# shield.net
KiCad netlist of a schematic drawn in Altium Designer
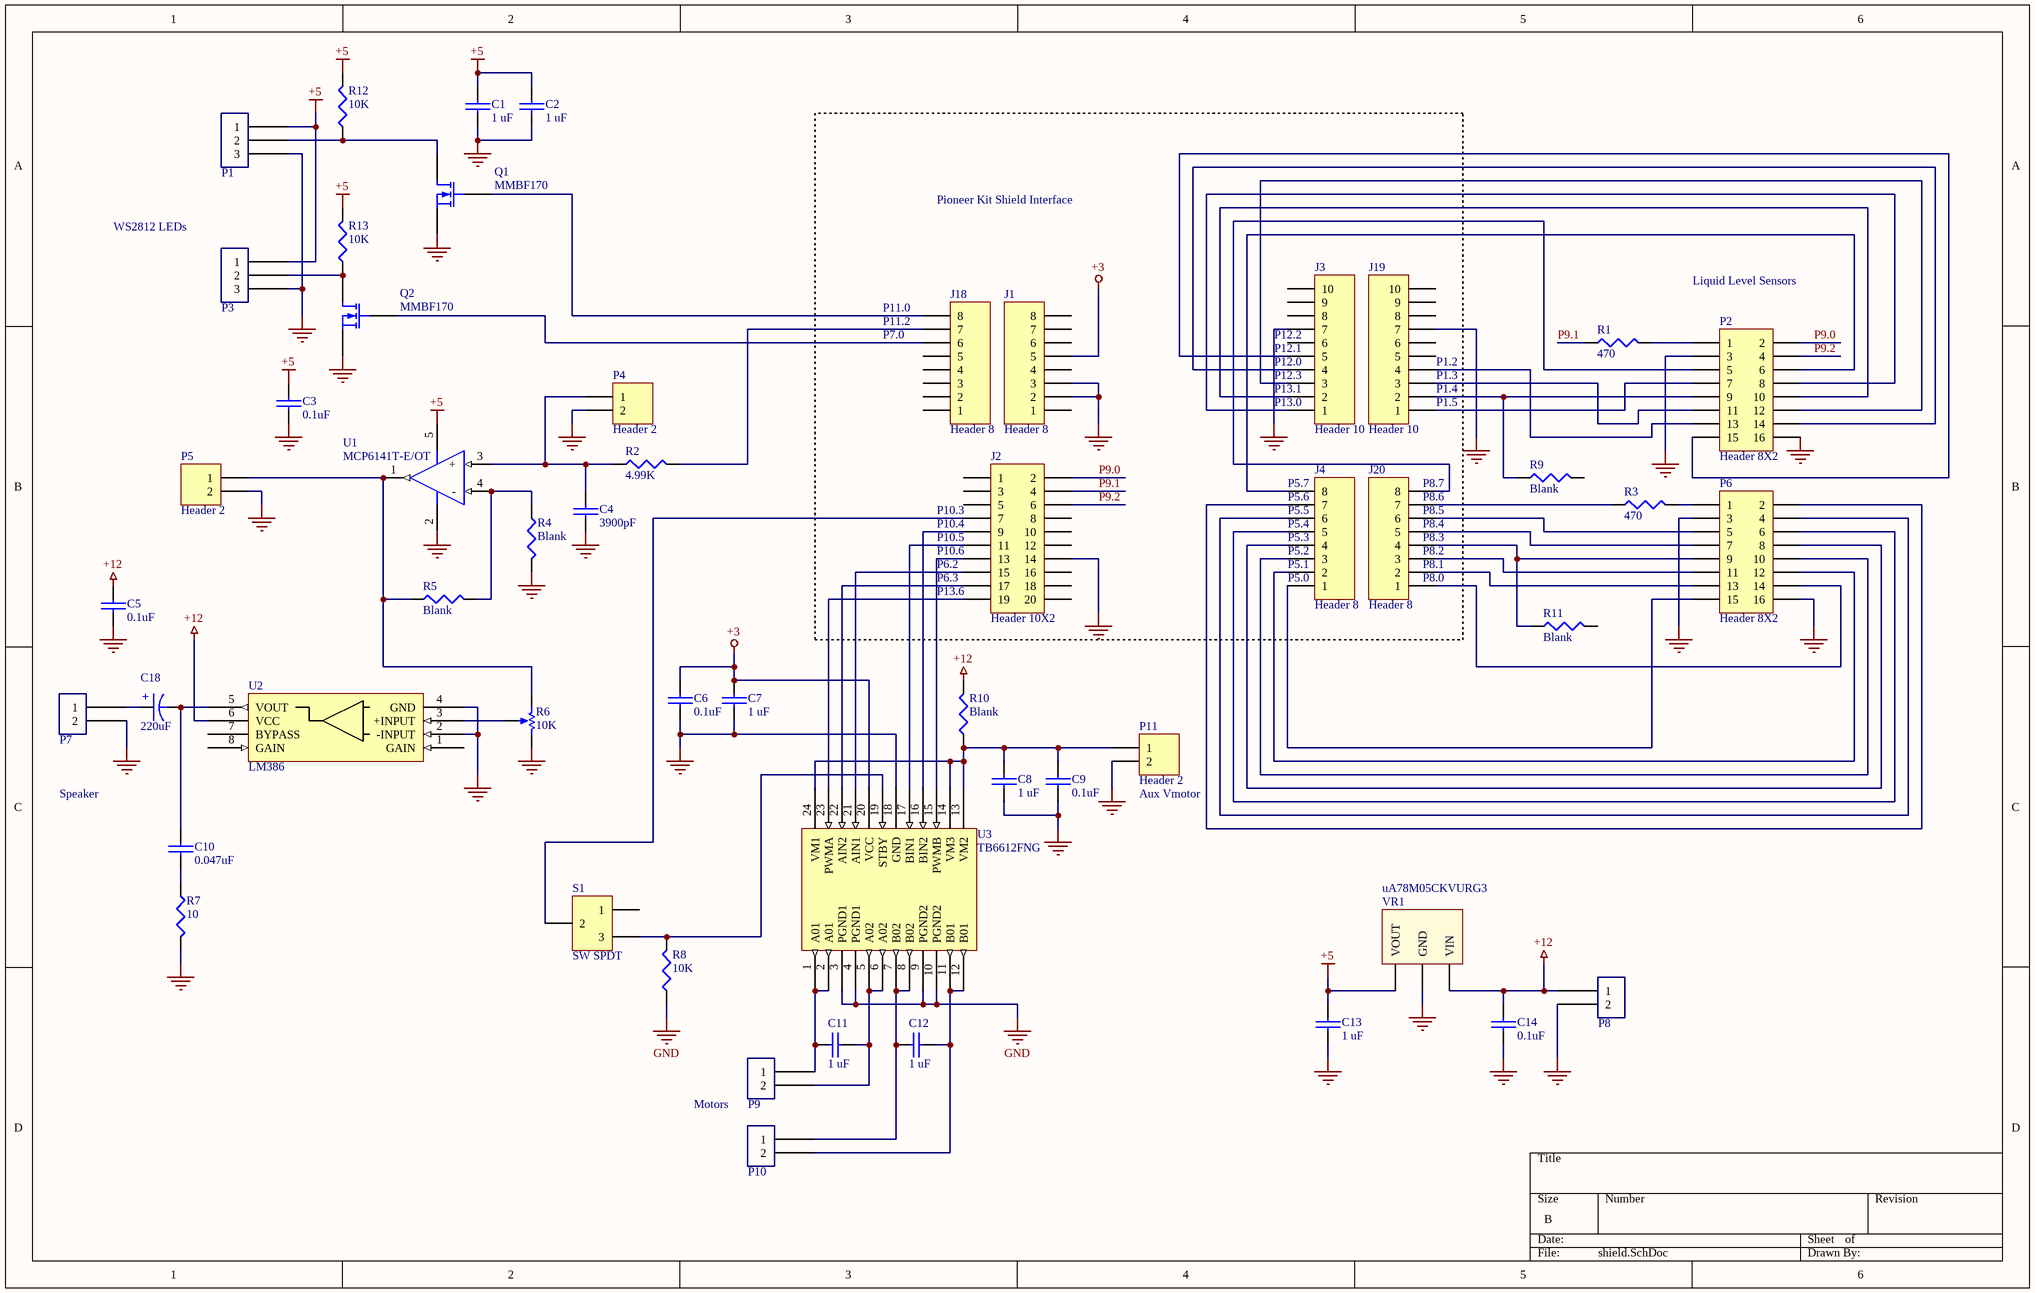
[diagram p0: shield.SchDoc]

(export (version "E")
  (design (tool "Eeschema 10.0.6"))
  (components
    (comp (ref "C1")
      (value "1 uF")
      (footprint "C0805")
      (description "CAP, CER, 1UF, 16v, 10%, X5R, 0805")
      (libsource (lib "phantron-discretes") (part "CAP, CER, 1UF, 0805"))
    )
    (comp (ref "C2")
      (value "1 uF")
      (footprint "C0805")
      (description "CAP, CER, 1UF, 16v, 10%, X5R, 0805")
      (libsource (lib "phantron-discretes") (part "CAP, CER, 1UF, 0805"))
    )
    (comp (ref "C3")
      (value "0.1uF")
      (footprint "C0603")
      (description "CAP, CER, 0.1UF, 50V, 10%, X7R, 0603")
      (libsource (lib "phantron-discretes") (part "CAP, CER, 0.1uF 0603"))
    )
    (comp (ref "C4")
      (value "3900pF")
      (footprint "C0603")
      (description "CAP, CER, blankUF, 6.3v, 10%, X5R, 0603")
      (libsource (lib "phantron-discretes") (part "CAP, CER, BLANK, 0603"))
    )
    (comp (ref "C5")
      (value "0.1uF")
      (footprint "C0603")
      (description "CAP, CER, 0.1UF, 50V, 10%, X7R, 0603")
      (libsource (lib "phantron-discretes") (part "CAP, CER, 0.1uF 0603"))
    )
    (comp (ref "C6")
      (value "0.1uF")
      (footprint "C0603")
      (description "CAP, CER, 0.1UF, 50V, 10%, X7R, 0603")
      (libsource (lib "phantron-discretes") (part "CAP, CER, 0.1uF 0603"))
    )
    (comp (ref "C7")
      (value "1 uF")
      (footprint "C0805")
      (description "CAP, CER, 1UF, 16v, 10%, X5R, 0805")
      (libsource (lib "phantron-discretes") (part "CAP, CER, 1UF, 0805"))
    )
    (comp (ref "C8")
      (value "1 uF")
      (footprint "C0805")
      (description "CAP, CER, 1UF, 16v, 10%, X5R, 0805")
      (libsource (lib "phantron-discretes") (part "CAP, CER, 1UF, 0805"))
    )
    (comp (ref "C9")
      (value "0.1uF")
      (footprint "C0603")
      (description "CAP, CER, 0.1UF, 50V, 10%, X7R, 0603")
      (libsource (lib "phantron-discretes") (part "CAP, CER, 0.1uF 0603"))
    )
    (comp (ref "C10")
      (value "0.047uF")
      (footprint "C0603")
      (description "CAP, CER, blankUF, 6.3v, 10%, X5R, 0603")
      (libsource (lib "phantron-discretes") (part "CAP, CER, BLANK, 0603"))
    )
    (comp (ref "C11")
      (value "1 uF")
      (footprint "C0805")
      (description "CAP, CER, 1UF, 16v, 10%, X5R, 0805")
      (libsource (lib "phantron-discretes") (part "CAP, CER, 1UF, 0805"))
    )
    (comp (ref "C12")
      (value "1 uF")
      (footprint "C0805")
      (description "CAP, CER, 1UF, 16v, 10%, X5R, 0805")
      (libsource (lib "phantron-discretes") (part "CAP, CER, 1UF, 0805"))
    )
    (comp (ref "C13")
      (value "1 uF")
      (footprint "C0805")
      (description "CAP, CER, 1UF, 16v, 10%, X5R, 0805")
      (libsource (lib "phantron-discretes") (part "CAP, CER, 1UF, 0805"))
    )
    (comp (ref "C14")
      (value "0.1uF")
      (footprint "C0603")
      (description "CAP, CER, 0.1UF, 50V, 10%, X7R, 0603")
      (libsource (lib "phantron-discretes") (part "CAP, CER, 0.1uF 0603"))
    )
    (comp (ref "C18")
      (value "220uF")
      (footprint "RadCap.98")
      (description "CAP, 220uF, 10V, ELEC, RAD")
      (fields (field (name "Comment") "11-000010-ARD"))
      (libsource (lib "00000000") (part "11-000010-ARD"))
    )
    (comp (ref "J1")
      (value "Header 8")
      (footprint "HDR1X8")
      (description "Header, 8-Pin")
      (fields (field (name "PUBLISHER") "Altium Limited"))
      (libsource (lib "Miscellaneous Connectors") (part "Header 8"))
    )
    (comp (ref "J2")
      (value "Header 10X2")
      (footprint "HDR2X10")
      (description "Header, 10-Pin, Dual row")
      (fields (field (name "PUBLISHER") "Altium Limited"))
      (libsource (lib "Miscellaneous Connectors") (part "Header 10X2"))
    )
    (comp (ref "J3")
      (value "Header 10")
      (footprint "HDR1X10")
      (description "Header, 10-Pin")
      (fields (field (name "PUBLISHER") "Altium Limited"))
      (libsource (lib "") (part "Header 10_1"))
    )
    (comp (ref "J4")
      (value "Header 8")
      (footprint "HDR1X8")
      (description "Header, 8-Pin")
      (fields (field (name "PUBLISHER") "Altium Limited"))
      (libsource (lib "") (part "Header 8_1"))
    )
    (comp (ref "J18")
      (value "Header 8")
      (footprint "HDR1X8")
      (description "Header, 8-Pin")
      (fields (field (name "PUBLISHER") "Altium Limited"))
      (libsource (lib "") (part "Header 8_1"))
    )
    (comp (ref "J19")
      (value "Header 10")
      (footprint "HDR1X10")
      (description "Header, 10-Pin")
      (fields (field (name "PUBLISHER") "Altium Limited"))
      (libsource (lib "Miscellaneous Connectors") (part "Header 10"))
    )
    (comp (ref "J20")
      (value "Header 8")
      (footprint "HDR1X8")
      (description "Header, 8-Pin")
      (fields (field (name "PUBLISHER") "Altium Limited"))
      (libsource (lib "Miscellaneous Connectors") (part "Header 8"))
    )
    (comp (ref "P1")
      (value "Connector, 0.138\", 3")
      (footprint "Phantron:connector-0.138-3pin")
      (description "Connector, 0.138\", 3 pin")
      (libsource (lib "Phantron") (part "Connector, 0.138{dblquote}, 3"))
    )
    (comp (ref "P2")
      (value "Header 8X2")
      (footprint "HDR2X8")
      (description "Header, 8-Pin, Dual row")
      (fields (field (name "PUBLISHER") "Altium Limited"))
      (libsource (lib "Miscellaneous Connectors") (part "Header 8X2"))
    )
    (comp (ref "P3")
      (value "Connector, 0.138\", 3")
      (footprint "Phantron:connector-0.138-3pin")
      (description "Connector, 0.138\", 3 pin")
      (libsource (lib "Phantron") (part "Connector, 0.138{dblquote}, 3"))
    )
    (comp (ref "P4")
      (value "Header 2")
      (footprint "HDR1X2")
      (description "Header, 2-Pin")
      (fields (field (name "PUBLISHER") "Altium Limited"))
      (libsource (lib "Miscellaneous Connectors") (part "Header 2"))
    )
    (comp (ref "P5")
      (value "Header 2")
      (footprint "HDR1X2")
      (description "Header, 2-Pin")
      (fields (field (name "PUBLISHER") "Altium Limited"))
      (libsource (lib "") (part "Header 2_1"))
    )
    (comp (ref "P6")
      (value "Header 8X2")
      (footprint "HDR2X8")
      (description "Header, 8-Pin, Dual row")
      (fields (field (name "PUBLISHER") "Altium Limited"))
      (libsource (lib "Miscellaneous Connectors") (part "Header 8X2"))
    )
    (comp (ref "P7")
      (value "Connector, 0.138\", 2")
      (footprint "Phantron:connector-0.138-2pin")
      (description "Connector, 0.138\", 2 pin")
      (libsource (lib "") (part "Connector, 0.138{dblquote}, 2_1"))
    )
    (comp (ref "P8")
      (value "Connector, 0.138\", 2")
      (footprint "Phantron:connector-0.138-2pin")
      (description "Connector, 0.138\", 2 pin")
      (libsource (lib "Phantron") (part "Connector, 0.138{dblquote}, 2"))
    )
    (comp (ref "P9")
      (value "Connector, 0.138\", 2")
      (footprint "Phantron:connector-0.138-2pin")
      (description "Connector, 0.138\", 2 pin")
      (libsource (lib "") (part "Connector, 0.138{dblquote}, 2_1"))
    )
    (comp (ref "P10")
      (value "Connector, 0.138\", 2")
      (footprint "Phantron:connector-0.138-2pin")
      (description "Connector, 0.138\", 2 pin")
      (libsource (lib "") (part "Connector, 0.138{dblquote}, 2_1"))
    )
    (comp (ref "P11")
      (value "Header 2")
      (footprint "HDR1X2")
      (description "Header, 2-Pin")
      (fields (field (name "PUBLISHER") "Altium Limited"))
      (libsource (lib "Miscellaneous Connectors") (part "Header 2"))
    )
    (comp (ref "Q1")
      (value "MMBF170")
      (footprint "SOT23")
      (description "MMBF170-7-F")
      (libsource (lib "Phantron") (part "MMBF170-7-F"))
    )
    (comp (ref "Q2")
      (value "MMBF170")
      (footprint "SOT23")
      (description "MMBF170-7-F")
      (libsource (lib "Phantron") (part "MMBF170-7-F"))
    )
    (comp (ref "R1")
      (value "470")
      (footprint "R0603")
      (description "RES, BLANK OHM, 1/10W, 1%, 0603 SMD")
      (libsource (lib "phantron-discretes") (part "RES, BLANK, 0603"))
    )
    (comp (ref "R2")
      (value "4.99K")
      (footprint "R0603")
      (description "RES, BLANK OHM, 1/10W, 1%, 0603 SMD")
      (libsource (lib "phantron-discretes") (part "RES, BLANK, 0603"))
    )
    (comp (ref "R3")
      (value "470")
      (footprint "R0603")
      (description "RES, BLANK OHM, 1/10W, 1%, 0603 SMD")
      (libsource (lib "phantron-discretes") (part "RES, BLANK, 0603"))
    )
    (comp (ref "R4")
      (value "Blank")
      (footprint "R0603")
      (description "RES, BLANK OHM, 1/10W, 1%, 0603 SMD")
      (libsource (lib "phantron-discretes") (part "RES, BLANK, 0603"))
    )
    (comp (ref "R5")
      (value "Blank")
      (footprint "R0603")
      (description "RES, BLANK OHM, 1/10W, 1%, 0603 SMD")
      (libsource (lib "phantron-discretes") (part "RES, BLANK, 0603"))
    )
    (comp (ref "R6")
      (value "10K")
      (footprint "TrimmerPot")
      (description "Potentiometer")
      (fields (field (name "Comment") "RPot") (field (name "PUBLISHER") "Altium Limited"))
      (libsource (lib "Miscellaneous Devices") (part "RPot"))
    )
    (comp (ref "R7")
      (value "10")
      (footprint "R0603")
      (description "RES, BLANK OHM, 1/10W, 1%, 0603 SMD")
      (libsource (lib "phantron-discretes") (part "RES, BLANK, 0603"))
    )
    (comp (ref "R8")
      (value "10K")
      (footprint "R0603")
      (description "RES, BLANK OHM, 1/10W, 1%, 0603 SMD")
      (libsource (lib "phantron-discretes") (part "RES, BLANK, 0603"))
    )
    (comp (ref "R9")
      (value "Blank")
      (footprint "R0603")
      (description "RES, BLANK OHM, 1/10W, 1%, 0603 SMD")
      (libsource (lib "phantron-discretes") (part "RES, BLANK, 0603"))
    )
    (comp (ref "R10")
      (value "Blank")
      (footprint "R0603")
      (description "RES, BLANK OHM, 1/10W, 1%, 0603 SMD")
      (libsource (lib "phantron-discretes") (part "RES, BLANK, 0603"))
    )
    (comp (ref "R11")
      (value "Blank")
      (footprint "R0603")
      (description "RES, BLANK OHM, 1/10W, 1%, 0603 SMD")
      (libsource (lib "phantron-discretes") (part "RES, BLANK, 0603"))
    )
    (comp (ref "R12")
      (value "10K")
      (footprint "R0603")
      (description "RES, BLANK OHM, 1/10W, 1%, 0603 SMD")
      (libsource (lib "phantron-discretes") (part "RES, BLANK, 0603"))
    )
    (comp (ref "R13")
      (value "10K")
      (footprint "R0603")
      (description "RES, BLANK OHM, 1/10W, 1%, 0603 SMD")
      (libsource (lib "phantron-discretes") (part "RES, BLANK, 0603"))
    )
    (comp (ref "S1")
      (value "SW SPDT")
      (footprint "HDR1X3")
      (description "Header, 3-Pin")
      (fields (field (name "PUBLISHER") "Altium Limited"))
      (libsource (lib "Miscellaneous Connectors") (part "Header 3"))
    )
    (comp (ref "U1")
      (value "MCP6141T-E/OT")
      (footprint "SOT23-5")
      (description "IC OPAMP SINGLE MCP6141 SOT23-5")
      (fields (field (name "MFG") "Microchip"))
      (libsource (lib "Phantron") (part "MCP6141"))
    )
    (comp (ref "U2")
      (value "LM386")
      (footprint "Phantron:SO8")
      (description "LM386MX")
      (fields (field (name "MFG") "TI"))
      (libsource (lib "Phantron") (part "LM386MX"))
    )
    (comp (ref "U3")
      (value "TB6612FNG")
      (footprint "Phantron:SSOP-24")
      (fields (field (name "MFG") "Toshiba"))
      (libsource (lib "Phantron") (part "TB6612FNG"))
    )
    (comp (ref "VR1")
      (value "uA78M05CKVURG3")
      (footprint "TO-252-AB(Dpak)")
      (libsource (lib "Phantron") (part "uA78M05CKVURG3"))
    )
  )
  (nets
    (net (code "1") (name "+3") (class "Default")
      (node (ref "C6") (pin "1") (pinfunction "A_1") (pintype "passive"))
      (node (ref "C7") (pin "1") (pinfunction "A_1") (pintype "passive"))
      (node (ref "J1") (pin "5") (pinfunction "5_5") (pintype "passive"))
      (node (ref "U3") (pin "20") (pinfunction "VCC_20") (pintype "power_in"))
    )
    (net (code "2") (name "+5") (class "Default")
      (node (ref "C1") (pin "1") (pinfunction "A_1") (pintype "passive"))
      (node (ref "C13") (pin "1") (pinfunction "A_1") (pintype "passive"))
      (node (ref "C2") (pin "1") (pinfunction "A_1") (pintype "passive"))
      (node (ref "C3") (pin "1") (pinfunction "A_1") (pintype "passive"))
      (node (ref "P1") (pin "1") (pinfunction "1_1") (pintype "passive"))
      (node (ref "P3") (pin "1") (pinfunction "1_1") (pintype "passive"))
      (node (ref "R12") (pin "2") (pinfunction "B_2") (pintype "passive"))
      (node (ref "R13") (pin "2") (pinfunction "B_2") (pintype "passive"))
      (node (ref "U1") (pin "5") (pinfunction "VCC_5") (pintype "power_in"))
      (node (ref "VR1") (pin "3") (pinfunction "VOUT_3") (pintype "passive"))
    )
    (net (code "3") (name "+12") (class "Default")
      (node (ref "C14") (pin "1") (pinfunction "A_1") (pintype "passive"))
      (node (ref "C5") (pin "1") (pinfunction "A_1") (pintype "passive"))
      (node (ref "P8") (pin "1") (pinfunction "1_1") (pintype "passive"))
      (node (ref "R10") (pin "2") (pinfunction "B_2") (pintype "passive"))
      (node (ref "U2") (pin "6") (pinfunction "VCC_6") (pintype "power_in"))
      (node (ref "VR1") (pin "1") (pinfunction "VIN_1") (pintype "passive"))
    )
    (net (code "4") (name "/P9.0") (class "Default")
      (node (ref "J2") (pin "2") (pinfunction "2_2") (pintype "passive"))
      (node (ref "P2") (pin "2") (pinfunction "2_2") (pintype "passive"))
    )
    (net (code "5") (name "/P9.1") (class "Default")
      (node (ref "J2") (pin "4") (pinfunction "4_4") (pintype "passive"))
      (node (ref "R1") (pin "1") (pinfunction "A_1") (pintype "passive"))
    )
    (net (code "6") (name "/P9.2") (class "Default")
      (node (ref "J2") (pin "6") (pinfunction "6_6") (pintype "passive"))
      (node (ref "P2") (pin "4") (pinfunction "4_4") (pintype "passive"))
    )
    (net (code "7") (name "GND") (class "Default")
      (node (ref "C1") (pin "2") (pinfunction "B_2") (pintype "passive"))
      (node (ref "C13") (pin "2") (pinfunction "B_2") (pintype "passive"))
      (node (ref "C14") (pin "2") (pinfunction "B_2") (pintype "passive"))
      (node (ref "C2") (pin "2") (pinfunction "B_2") (pintype "passive"))
      (node (ref "C3") (pin "2") (pinfunction "B_2") (pintype "passive"))
      (node (ref "C4") (pin "2") (pinfunction "B_2") (pintype "passive"))
      (node (ref "C5") (pin "2") (pinfunction "B_2") (pintype "passive"))
      (node (ref "C6") (pin "2") (pinfunction "B_2") (pintype "passive"))
      (node (ref "C7") (pin "2") (pinfunction "B_2") (pintype "passive"))
      (node (ref "C8") (pin "2") (pinfunction "B_2") (pintype "passive"))
      (node (ref "C9") (pin "2") (pinfunction "B_2") (pintype "passive"))
      (node (ref "J1") (pin "2") (pinfunction "2_2") (pintype "passive"))
      (node (ref "J1") (pin "3") (pinfunction "3_3") (pintype "passive"))
      (node (ref "J19") (pin "7") (pinfunction "7_7") (pintype "passive"))
      (node (ref "J2") (pin "14") (pinfunction "14_14") (pintype "passive"))
      (node (ref "J3") (pin "7") (pinfunction "7_7") (pintype "passive"))
      (node (ref "P1") (pin "3") (pinfunction "3_3") (pintype "passive"))
      (node (ref "P11") (pin "2") (pinfunction "2_2") (pintype "passive"))
      (node (ref "P2") (pin "16") (pinfunction "16_16") (pintype "passive"))
      (node (ref "P2") (pin "3") (pinfunction "3_3") (pintype "passive"))
      (node (ref "P3") (pin "3") (pinfunction "3_3") (pintype "passive"))
      (node (ref "P4") (pin "2") (pinfunction "2_2") (pintype "passive"))
      (node (ref "P5") (pin "2") (pinfunction "2_2") (pintype "passive"))
      (node (ref "P6") (pin "16") (pinfunction "16_16") (pintype "passive"))
      (node (ref "P6") (pin "3") (pinfunction "3_3") (pintype "passive"))
      (node (ref "P7") (pin "2") (pinfunction "2_2") (pintype "passive"))
      (node (ref "P8") (pin "2") (pinfunction "2_2") (pintype "passive"))
      (node (ref "Q1") (pin "2") (pinfunction "S_2") (pintype "passive"))
      (node (ref "Q2") (pin "2") (pinfunction "S_2") (pintype "passive"))
      (node (ref "R4") (pin "2") (pinfunction "B_2") (pintype "passive"))
      (node (ref "R6") (pin "1") (pinfunction "TOP_1") (pintype "passive"))
      (node (ref "R7") (pin "2") (pinfunction "B_2") (pintype "passive"))
      (node (ref "R8") (pin "1") (pinfunction "A_1") (pintype "passive"))
      (node (ref "U1") (pin "2") (pinfunction "GND_2") (pintype "power_in"))
      (node (ref "U2") (pin "2") (pinfunction "-INPUT_2") (pintype "input"))
      (node (ref "U2") (pin "4") (pinfunction "GND_4") (pintype "power_in"))
      (node (ref "U3") (pin "10") (pinfunction "PGND2_10") (pintype "power_in"))
      (node (ref "U3") (pin "18") (pinfunction "GND_18") (pintype "power_in"))
      (node (ref "U3") (pin "3") (pinfunction "PGND1_3") (pintype "power_in"))
      (node (ref "U3") (pin "4") (pinfunction "PGND1_4") (pintype "power_in"))
      (node (ref "U3") (pin "9") (pinfunction "PGND2_9") (pintype "power_in"))
      (node (ref "VR1") (pin "4") (pinfunction "GND_4") (pintype "passive"))
    )
    (net (code "8") (name "Net-(C4-A)") (class "Default")
      (node (ref "C4") (pin "1") (pinfunction "A_1") (pintype "passive"))
      (node (ref "P4") (pin "1") (pinfunction "1_1") (pintype "passive"))
      (node (ref "R2") (pin "1") (pinfunction "A_1") (pintype "passive"))
      (node (ref "U1") (pin "3") (pinfunction "+_3") (pintype "input"))
    )
    (net (code "9") (name "Net-(C8-A)") (class "Default")
      (node (ref "C8") (pin "1") (pinfunction "A_1") (pintype "passive"))
      (node (ref "C9") (pin "1") (pinfunction "A_1") (pintype "passive"))
      (node (ref "P11") (pin "1") (pinfunction "1_1") (pintype "passive"))
      (node (ref "R10") (pin "1") (pinfunction "A_1") (pintype "passive"))
      (node (ref "U3") (pin "13") (pinfunction "VM2_13") (pintype "power_in"))
      (node (ref "U3") (pin "14") (pinfunction "VM3_14") (pintype "power_in"))
      (node (ref "U3") (pin "24") (pinfunction "VM1_24") (pintype "power_in"))
    )
    (net (code "10") (name "Net-(C10-A)") (class "Default")
      (node (ref "C10") (pin "1") (pinfunction "A_1") (pintype "passive"))
      (node (ref "C18") (pin "2") (pinfunction "NEGATIVE_2") (pintype "passive"))
      (node (ref "U2") (pin "5") (pinfunction "VOUT_5") (pintype "output"))
    )
    (net (code "11") (name "Net-(C10-B)") (class "Default")
      (node (ref "C10") (pin "2") (pinfunction "B_2") (pintype "passive"))
      (node (ref "R7") (pin "1") (pinfunction "A_1") (pintype "passive"))
    )
    (net (code "12") (name "Net-(C11-A)") (class "Default")
      (node (ref "C11") (pin "1") (pinfunction "A_1") (pintype "passive"))
      (node (ref "P9") (pin "1") (pinfunction "1_1") (pintype "passive"))
      (node (ref "U3") (pin "1") (pinfunction "A01_1") (pintype "output"))
      (node (ref "U3") (pin "2") (pinfunction "A01_2") (pintype "output"))
    )
    (net (code "13") (name "Net-(C11-B)") (class "Default")
      (node (ref "C11") (pin "2") (pinfunction "B_2") (pintype "passive"))
      (node (ref "P9") (pin "2") (pinfunction "2_2") (pintype "passive"))
      (node (ref "U3") (pin "5") (pinfunction "A02_5") (pintype "output"))
      (node (ref "U3") (pin "6") (pinfunction "A02_6") (pintype "output"))
    )
    (net (code "14") (name "Net-(C12-A)") (class "Default")
      (node (ref "C12") (pin "1") (pinfunction "A_1") (pintype "passive"))
      (node (ref "P10") (pin "1") (pinfunction "1_1") (pintype "passive"))
      (node (ref "U3") (pin "7") (pinfunction "B02_7") (pintype "output"))
      (node (ref "U3") (pin "8") (pinfunction "B02_8") (pintype "output"))
    )
    (net (code "15") (name "Net-(C12-B)") (class "Default")
      (node (ref "C12") (pin "2") (pinfunction "B_2") (pintype "passive"))
      (node (ref "P10") (pin "2") (pinfunction "2_2") (pintype "passive"))
      (node (ref "U3") (pin "11") (pinfunction "B01_11") (pintype "output"))
      (node (ref "U3") (pin "12") (pinfunction "B01_12") (pintype "output"))
    )
    (net (code "16") (name "Net-(C18-POSITIVE)") (class "Default")
      (node (ref "C18") (pin "1") (pinfunction "POSITIVE_1") (pintype "passive"))
      (node (ref "P7") (pin "1") (pinfunction "1_1") (pintype "passive"))
    )
    (net (code "17") (name "Net-(J2-Pad7)") (class "Default")
      (node (ref "J2") (pin "7") (pinfunction "7_7") (pintype "passive"))
      (node (ref "S1") (pin "2") (pinfunction "2_2") (pintype "passive"))
    )
    (net (code "18") (name "Net-(J3-Pad1)") (class "Default")
      (node (ref "J3") (pin "1") (pinfunction "1_1") (pintype "passive"))
      (node (ref "P2") (pin "8") (pinfunction "8_8") (pintype "passive"))
    )
    (net (code "19") (name "Net-(J3-Pad2)") (class "Default")
      (node (ref "J3") (pin "2") (pinfunction "2_2") (pintype "passive"))
      (node (ref "P2") (pin "10") (pinfunction "10_10") (pintype "passive"))
    )
    (net (code "20") (name "Net-(J3-Pad3)") (class "Default")
      (node (ref "J3") (pin "3") (pinfunction "3_3") (pintype "passive"))
      (node (ref "P2") (pin "12") (pinfunction "12_12") (pintype "passive"))
    )
    (net (code "21") (name "Net-(J3-Pad4)") (class "Default")
      (node (ref "J3") (pin "4") (pinfunction "4_4") (pintype "passive"))
      (node (ref "P2") (pin "14") (pinfunction "14_14") (pintype "passive"))
    )
    (net (code "22") (name "Net-(J3-Pad5)") (class "Default")
      (node (ref "J3") (pin "5") (pinfunction "5_5") (pintype "passive"))
      (node (ref "P2") (pin "15") (pinfunction "15_15") (pintype "passive"))
    )
    (net (code "23") (name "Net-(J4-Pad1)") (class "Default")
      (node (ref "J4") (pin "1") (pinfunction "1_1") (pintype "passive"))
      (node (ref "P6") (pin "15") (pinfunction "15_15") (pintype "passive"))
    )
    (net (code "24") (name "Net-(J4-Pad2)") (class "Default")
      (node (ref "J4") (pin "2") (pinfunction "2_2") (pintype "passive"))
      (node (ref "P6") (pin "12") (pinfunction "12_12") (pintype "passive"))
    )
    (net (code "25") (name "Net-(J4-Pad3)") (class "Default")
      (node (ref "J4") (pin "3") (pinfunction "3_3") (pintype "passive"))
      (node (ref "P6") (pin "10") (pinfunction "10_10") (pintype "passive"))
    )
    (net (code "26") (name "Net-(J4-Pad4)") (class "Default")
      (node (ref "J4") (pin "4") (pinfunction "4_4") (pintype "passive"))
      (node (ref "P6") (pin "8") (pinfunction "8_8") (pintype "passive"))
    )
    (net (code "27") (name "Net-(J4-Pad5)") (class "Default")
      (node (ref "J4") (pin "5") (pinfunction "5_5") (pintype "passive"))
      (node (ref "P6") (pin "6") (pinfunction "6_6") (pintype "passive"))
    )
    (net (code "28") (name "Net-(J4-Pad6)") (class "Default")
      (node (ref "J4") (pin "6") (pinfunction "6_6") (pintype "passive"))
      (node (ref "P6") (pin "4") (pinfunction "4_4") (pintype "passive"))
    )
    (net (code "29") (name "Net-(J4-Pad7)") (class "Default")
      (node (ref "J4") (pin "7") (pinfunction "7_7") (pintype "passive"))
      (node (ref "P6") (pin "2") (pinfunction "2_2") (pintype "passive"))
    )
    (net (code "30") (name "Net-(J4-Pad8)") (class "Default")
      (node (ref "J4") (pin "8") (pinfunction "8_8") (pintype "passive"))
      (node (ref "P2") (pin "6") (pinfunction "6_6") (pintype "passive"))
    )
    (net (code "31") (name "Net-(J19-Pad1)") (class "Default")
      (node (ref "J19") (pin "1") (pinfunction "1_1") (pintype "passive"))
      (node (ref "P2") (pin "7") (pinfunction "7_7") (pintype "passive"))
    )
    (net (code "32") (name "Net-(J19-Pad3)") (class "Default")
      (node (ref "J19") (pin "3") (pinfunction "3_3") (pintype "passive"))
      (node (ref "P2") (pin "11") (pinfunction "11_11") (pintype "passive"))
    )
    (net (code "33") (name "Net-(J19-Pad4)") (class "Default")
      (node (ref "J19") (pin "4") (pinfunction "4_4") (pintype "passive"))
      (node (ref "P2") (pin "13") (pinfunction "13_13") (pintype "passive"))
    )
    (net (code "34") (name "Net-(J20-Pad1)") (class "Default")
      (node (ref "J20") (pin "1") (pinfunction "1_1") (pintype "passive"))
      (node (ref "P6") (pin "14") (pinfunction "14_14") (pintype "passive"))
    )
    (net (code "35") (name "Net-(J20-Pad2)") (class "Default")
      (node (ref "J20") (pin "2") (pinfunction "2_2") (pintype "passive"))
      (node (ref "P6") (pin "13") (pinfunction "13_13") (pintype "passive"))
    )
    (net (code "36") (name "Net-(J20-Pad3)") (class "Default")
      (node (ref "J20") (pin "3") (pinfunction "3_3") (pintype "passive"))
      (node (ref "P6") (pin "11") (pinfunction "11_11") (pintype "passive"))
    )
    (net (code "37") (name "Net-(J20-Pad5)") (class "Default")
      (node (ref "J20") (pin "5") (pinfunction "5_5") (pintype "passive"))
      (node (ref "P6") (pin "7") (pinfunction "7_7") (pintype "passive"))
    )
    (net (code "38") (name "Net-(J20-Pad6)") (class "Default")
      (node (ref "J20") (pin "6") (pinfunction "6_6") (pintype "passive"))
      (node (ref "P6") (pin "5") (pinfunction "5_5") (pintype "passive"))
    )
    (net (code "39") (name "Net-(J20-Pad8)") (class "Default")
      (node (ref "J20") (pin "8") (pinfunction "8_8") (pintype "passive"))
      (node (ref "P2") (pin "5") (pinfunction "5_5") (pintype "passive"))
    )
    (net (code "40") (name "Net-(Q1-D)") (class "Default")
      (node (ref "P1") (pin "2") (pinfunction "2_2") (pintype "passive"))
      (node (ref "Q1") (pin "3") (pinfunction "D_3") (pintype "passive"))
      (node (ref "R12") (pin "1") (pinfunction "A_1") (pintype "passive"))
    )
    (net (code "41") (name "Net-(Q1-G)") (class "Default")
      (node (ref "J18") (pin "8") (pinfunction "8_8") (pintype "passive"))
      (node (ref "Q1") (pin "1") (pinfunction "G_1") (pintype "passive"))
    )
    (net (code "42") (name "Net-(Q2-D)") (class "Default")
      (node (ref "P3") (pin "2") (pinfunction "2_2") (pintype "passive"))
      (node (ref "Q2") (pin "3") (pinfunction "D_3") (pintype "passive"))
      (node (ref "R13") (pin "1") (pinfunction "A_1") (pintype "passive"))
    )
    (net (code "43") (name "Net-(Q2-G)") (class "Default")
      (node (ref "J18") (pin "6") (pinfunction "6_6") (pintype "passive"))
      (node (ref "Q2") (pin "1") (pinfunction "G_1") (pintype "passive"))
    )
    (net (code "44") (name "Net-(R1-B)") (class "Default")
      (node (ref "P2") (pin "1") (pinfunction "1_1") (pintype "passive"))
      (node (ref "R1") (pin "2") (pinfunction "B_2") (pintype "passive"))
    )
    (net (code "45") (name "Net-(R2-B)") (class "Default")
      (node (ref "J18") (pin "7") (pinfunction "7_7") (pintype "passive"))
      (node (ref "R2") (pin "2") (pinfunction "B_2") (pintype "passive"))
    )
    (net (code "46") (name "Net-(R3-A)") (class "Default")
      (node (ref "J20") (pin "7") (pinfunction "7_7") (pintype "passive"))
      (node (ref "R3") (pin "1") (pinfunction "A_1") (pintype "passive"))
    )
    (net (code "47") (name "Net-(R3-B)") (class "Default")
      (node (ref "P6") (pin "1") (pinfunction "1_1") (pintype "passive"))
      (node (ref "R3") (pin "2") (pinfunction "B_2") (pintype "passive"))
    )
    (net (code "48") (name "Net-(R4-A)") (class "Default")
      (node (ref "R4") (pin "1") (pinfunction "A_1") (pintype "passive"))
      (node (ref "R5") (pin "2") (pinfunction "B_2") (pintype "passive"))
      (node (ref "U1") (pin "4") (pinfunction "-_4") (pintype "input"))
    )
    (net (code "49") (name "Net-(R5-A)") (class "Default")
      (node (ref "P5") (pin "1") (pinfunction "1_1") (pintype "passive"))
      (node (ref "R5") (pin "1") (pinfunction "A_1") (pintype "passive"))
      (node (ref "R6") (pin "3") (pinfunction "BOT_3") (pintype "passive"))
      (node (ref "U1") (pin "1") (pinfunction "OUT_1") (pintype "output"))
    )
    (net (code "50") (name "Net-(R6-TAP)") (class "Default")
      (node (ref "R6") (pin "2") (pinfunction "TAP_2") (pintype "passive"))
      (node (ref "U2") (pin "3") (pinfunction "+INPUT_3") (pintype "input"))
    )
    (net (code "51") (name "Net-(R8-B)") (class "Default")
      (node (ref "R8") (pin "2") (pinfunction "B_2") (pintype "passive"))
      (node (ref "S1") (pin "3") (pinfunction "3_3") (pintype "passive"))
      (node (ref "U3") (pin "19") (pinfunction "STBY_19") (pintype "input"))
    )
    (net (code "52") (name "Net-(R9-A)") (class "Default")
      (node (ref "J19") (pin "2") (pinfunction "2_2") (pintype "passive"))
      (node (ref "P2") (pin "9") (pinfunction "9_9") (pintype "passive"))
      (node (ref "R9") (pin "1") (pinfunction "A_1") (pintype "passive"))
    )
    (net (code "53") (name "Net-(R11-A)") (class "Default")
      (node (ref "J20") (pin "4") (pinfunction "4_4") (pintype "passive"))
      (node (ref "P6") (pin "9") (pinfunction "9_9") (pintype "passive"))
      (node (ref "R11") (pin "1") (pinfunction "A_1") (pintype "passive"))
    )
    (net (code "54") (name "Net-(U3-AIN1)") (class "Default")
      (node (ref "J2") (pin "15") (pinfunction "15_15") (pintype "passive"))
      (node (ref "U3") (pin "21") (pinfunction "AIN1_21") (pintype "input"))
    )
    (net (code "55") (name "Net-(U3-AIN2)") (class "Default")
      (node (ref "J2") (pin "17") (pinfunction "17_17") (pintype "passive"))
      (node (ref "U3") (pin "22") (pinfunction "AIN2_22") (pintype "input"))
    )
    (net (code "56") (name "Net-(U3-BIN1)") (class "Default")
      (node (ref "J2") (pin "11") (pinfunction "11_11") (pintype "passive"))
      (node (ref "U3") (pin "17") (pinfunction "BIN1_17") (pintype "input"))
    )
    (net (code "57") (name "Net-(U3-BIN2)") (class "Default")
      (node (ref "J2") (pin "9") (pinfunction "9_9") (pintype "passive"))
      (node (ref "U3") (pin "16") (pinfunction "BIN2_16") (pintype "input"))
    )
    (net (code "58") (name "Net-(U3-PWMA)") (class "Default")
      (node (ref "J2") (pin "19") (pinfunction "19_19") (pintype "passive"))
      (node (ref "U3") (pin "23") (pinfunction "PWMA_23") (pintype "input"))
    )
    (net (code "59") (name "Net-(U3-PWMB)") (class "Default")
      (node (ref "J2") (pin "13") (pinfunction "13_13") (pintype "passive"))
      (node (ref "U3") (pin "15") (pinfunction "PWMB_15") (pintype "input"))
    )
    (net (code "60") (name "unconnected-(J1-Pad1)") (class "Default")
      (node (ref "J1") (pin "1") (pinfunction "1_1") (pintype "passive"))
    )
    (net (code "61") (name "unconnected-(J1-Pad4)") (class "Default")
      (node (ref "J1") (pin "4") (pinfunction "4_4") (pintype "passive"))
    )
    (net (code "62") (name "unconnected-(J1-Pad6)") (class "Default")
      (node (ref "J1") (pin "6") (pinfunction "6_6") (pintype "passive"))
    )
    (net (code "63") (name "unconnected-(J1-Pad7)") (class "Default")
      (node (ref "J1") (pin "7") (pinfunction "7_7") (pintype "passive"))
    )
    (net (code "64") (name "unconnected-(J1-Pad8)") (class "Default")
      (node (ref "J1") (pin "8") (pinfunction "8_8") (pintype "passive"))
    )
    (net (code "65") (name "unconnected-(J2-Pad1)") (class "Default")
      (node (ref "J2") (pin "1") (pinfunction "1_1") (pintype "passive"))
    )
    (net (code "66") (name "unconnected-(J2-Pad3)") (class "Default")
      (node (ref "J2") (pin "3") (pinfunction "3_3") (pintype "passive"))
    )
    (net (code "67") (name "unconnected-(J2-Pad5)") (class "Default")
      (node (ref "J2") (pin "5") (pinfunction "5_5") (pintype "passive"))
    )
    (net (code "68") (name "unconnected-(J2-Pad8)") (class "Default")
      (node (ref "J2") (pin "8") (pinfunction "8_8") (pintype "passive"))
    )
    (net (code "69") (name "unconnected-(J2-Pad10)") (class "Default")
      (node (ref "J2") (pin "10") (pinfunction "10_10") (pintype "passive"))
    )
    (net (code "70") (name "unconnected-(J2-Pad12)") (class "Default")
      (node (ref "J2") (pin "12") (pinfunction "12_12") (pintype "passive"))
    )
    (net (code "71") (name "unconnected-(J2-Pad16)") (class "Default")
      (node (ref "J2") (pin "16") (pinfunction "16_16") (pintype "passive"))
    )
    (net (code "72") (name "unconnected-(J2-Pad18)") (class "Default")
      (node (ref "J2") (pin "18") (pinfunction "18_18") (pintype "passive"))
    )
    (net (code "73") (name "unconnected-(J2-Pad20)") (class "Default")
      (node (ref "J2") (pin "20") (pinfunction "20_20") (pintype "passive"))
    )
    (net (code "74") (name "unconnected-(J3-Pad6)") (class "Default")
      (node (ref "J3") (pin "6") (pinfunction "6_6") (pintype "passive"))
    )
    (net (code "75") (name "unconnected-(J3-Pad8)") (class "Default")
      (node (ref "J3") (pin "8") (pinfunction "8_8") (pintype "passive"))
    )
    (net (code "76") (name "unconnected-(J3-Pad9)") (class "Default")
      (node (ref "J3") (pin "9") (pinfunction "9_9") (pintype "passive"))
    )
    (net (code "77") (name "unconnected-(J3-Pad10)") (class "Default")
      (node (ref "J3") (pin "10") (pinfunction "10_10") (pintype "passive"))
    )
    (net (code "78") (name "unconnected-(J18-Pad1)") (class "Default")
      (node (ref "J18") (pin "1") (pinfunction "1_1") (pintype "passive"))
    )
    (net (code "79") (name "unconnected-(J18-Pad2)") (class "Default")
      (node (ref "J18") (pin "2") (pinfunction "2_2") (pintype "passive"))
    )
    (net (code "80") (name "unconnected-(J18-Pad3)") (class "Default")
      (node (ref "J18") (pin "3") (pinfunction "3_3") (pintype "passive"))
    )
    (net (code "81") (name "unconnected-(J18-Pad4)") (class "Default")
      (node (ref "J18") (pin "4") (pinfunction "4_4") (pintype "passive"))
    )
    (net (code "82") (name "unconnected-(J18-Pad5)") (class "Default")
      (node (ref "J18") (pin "5") (pinfunction "5_5") (pintype "passive"))
    )
    (net (code "83") (name "unconnected-(J19-Pad5)") (class "Default")
      (node (ref "J19") (pin "5") (pinfunction "5_5") (pintype "passive"))
    )
    (net (code "84") (name "unconnected-(J19-Pad6)") (class "Default")
      (node (ref "J19") (pin "6") (pinfunction "6_6") (pintype "passive"))
    )
    (net (code "85") (name "unconnected-(J19-Pad8)") (class "Default")
      (node (ref "J19") (pin "8") (pinfunction "8_8") (pintype "passive"))
    )
    (net (code "86") (name "unconnected-(J19-Pad9)") (class "Default")
      (node (ref "J19") (pin "9") (pinfunction "9_9") (pintype "passive"))
    )
    (net (code "87") (name "unconnected-(J19-Pad10)") (class "Default")
      (node (ref "J19") (pin "10") (pinfunction "10_10") (pintype "passive"))
    )
    (net (code "88") (name "unconnected-(R9-B-Pad2)") (class "Default")
      (node (ref "R9") (pin "2") (pinfunction "B_2") (pintype "passive"))
    )
    (net (code "89") (name "unconnected-(R11-B-Pad2)") (class "Default")
      (node (ref "R11") (pin "2") (pinfunction "B_2") (pintype "passive"))
    )
    (net (code "90") (name "unconnected-(S1-Pad1)") (class "Default")
      (node (ref "S1") (pin "1") (pinfunction "1_1") (pintype "passive"))
    )
    (net (code "91") (name "unconnected-(U2-BYPASS-Pad7)") (class "Default")
      (node (ref "U2") (pin "7") (pinfunction "BYPASS_7") (pintype "passive"))
    )
    (net (code "92") (name "unconnected-(U2-GAIN-Pad1)") (class "Default")
      (node (ref "U2") (pin "1") (pinfunction "GAIN_1") (pintype "input"))
    )
    (net (code "93") (name "unconnected-(U2-GAIN-Pad8)") (class "Default")
      (node (ref "U2") (pin "8") (pinfunction "GAIN_8") (pintype "input"))
    )
  )
)
